# Arduino_extension_connectors.net
KiCad netlist of a schematic drawn in Altium Designer
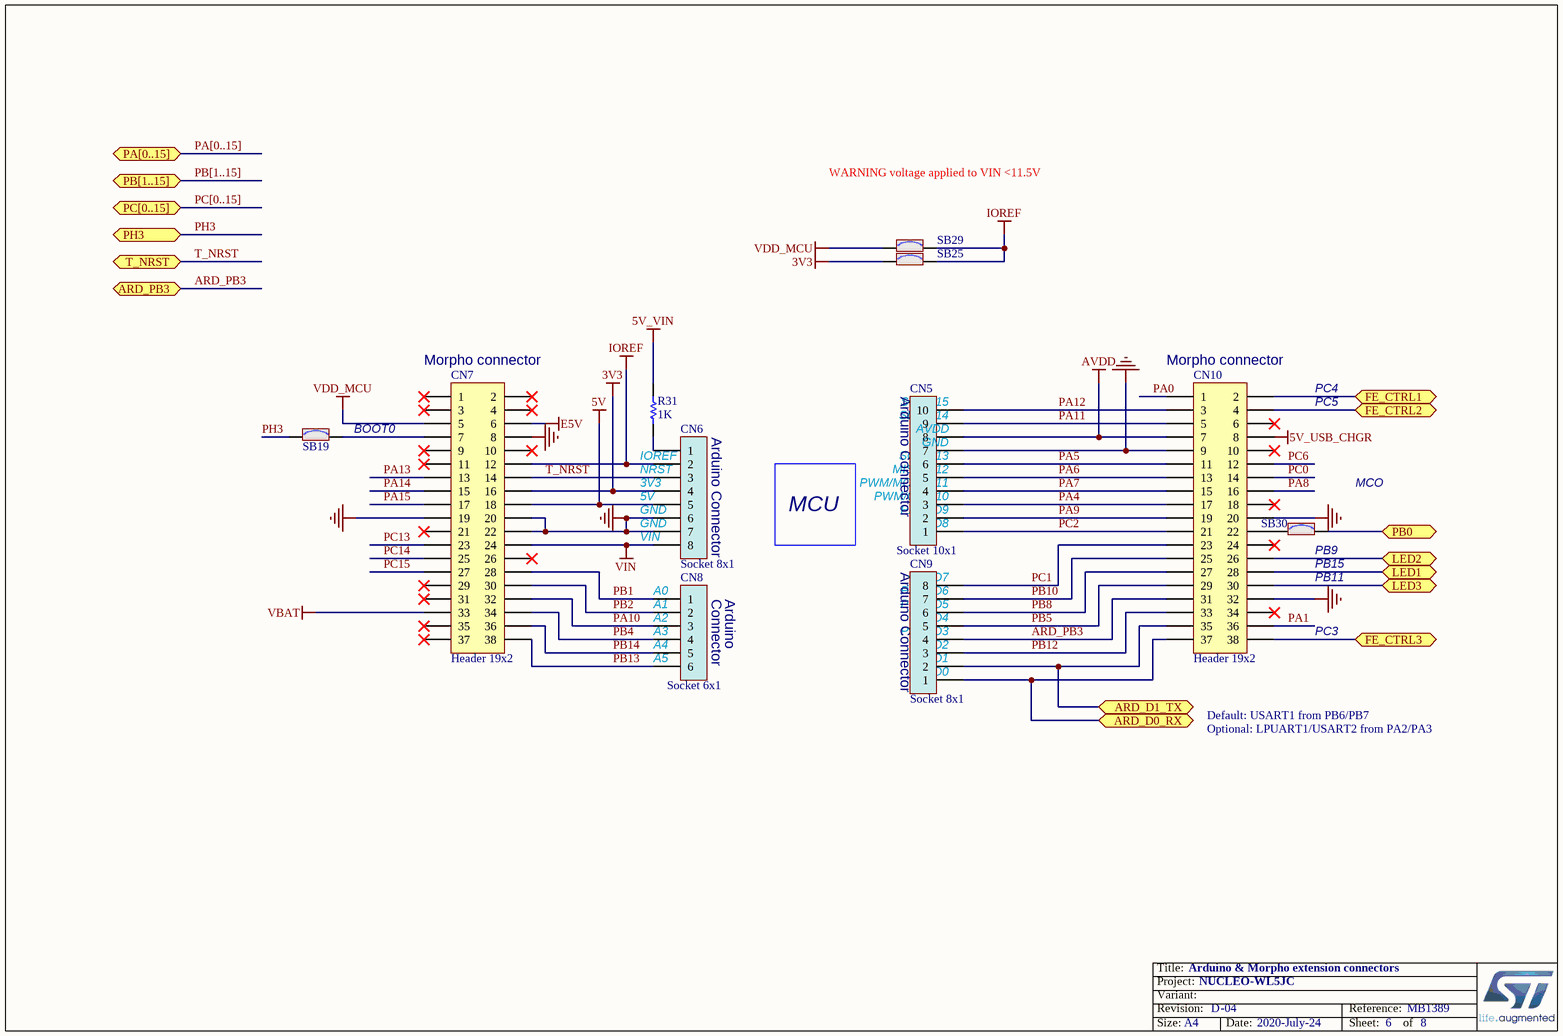
[diagram p0: Arduino_extension_connectors.SchDoc]

(export (version "E")
  (design (tool "Eeschema 10.0.6"))
  (components
    (comp (ref "CN5")
      (value "Socket 10x1")
      (footprint "CON_SAMTEC_SSW-110-03-X-S")
      (description "Socket, 10x1, 2.54mm, VR, TH, Height 8.51mm/10mm")
      (fields
        (field (name "INTERNAL_PART_NUMBER") "MCD-00262")
        (field (name "MANUFACTURER_PART_NUMBER") "SSW-110-03-x-S")
        (field (name "PROVIDED_BY") "SUBCO")
      )
      (libsource (lib "MCD_PARTS_database") (part "Socket 10x1"))
    )
    (comp (ref "CN6")
      (value "Socket 8x1")
      (footprint "CON_SAMTEC_SSW-108-03-X-S")
      (description "Socket, 8x1, 2.54mm, VR, TH, Height 8.51mm/10mm")
      (fields
        (field (name "INTERNAL_PART_NUMBER") "MCD-00261")
        (field (name "MANUFACTURER_PART_NUMBER") "SSW-108-03-x-S")
        (field (name "PROVIDED_BY") "SUBCO")
      )
      (libsource (lib "") (part "Socket 8x1_1"))
    )
    (comp (ref "CN7")
      (value "Header 19x2")
      (footprint "CON_SAMTEC_TSW-119-09-X-D")
      (description "Header, 19x2, 2,54mm, VR, TH, Height 5.84mm/10.16mm")
      (fields
        (field (name "INTERNAL_PART_NUMBER") "MCD-00213")
        (field (name "MANUFACTURER_PART_NUMBER") "TSW-119-09-x-D")
        (field (name "PROVIDED_BY") "SUBCO")
      )
      (libsource (lib "MCD_PARTS_database") (part "Header 19x2"))
    )
    (comp (ref "CN8")
      (value "Socket 6x1")
      (footprint "CON_SAMTEC_SSW-106-03-X-S")
      (description "Socket, 6x1, 2.54mm, VR, TH, Height 8.51mm/10mm")
      (fields
        (field (name "INTERNAL_PART_NUMBER") "MCD-00260")
        (field (name "MANUFACTURER_PART_NUMBER") "SSW-106-03-x-S")
        (field (name "PROVIDED_BY") "SUBCO")
      )
      (libsource (lib "MCD_PARTS_database") (part "Socket 6x1"))
    )
    (comp (ref "CN9")
      (value "Socket 8x1")
      (footprint "CON_SAMTEC_SSW-108-03-X-S")
      (description "Socket, 8x1, 2.54mm, VR, TH, Height 8.51mm/10mm")
      (fields
        (field (name "INTERNAL_PART_NUMBER") "MCD-00261")
        (field (name "MANUFACTURER_PART_NUMBER") "SSW-108-03-x-S")
        (field (name "PROVIDED_BY") "SUBCO")
      )
      (libsource (lib "MCD_PARTS_database") (part "Socket 8x1"))
    )
    (comp (ref "CN10")
      (value "Header 19x2")
      (footprint "CON_SAMTEC_TSW-119-09-X-D")
      (description "Header, 19x2, 2,54mm, VR, TH, Height 5.84mm/10.16mm")
      (fields
        (field (name "INTERNAL_PART_NUMBER") "MCD-00213")
        (field (name "MANUFACTURER_PART_NUMBER") "TSW-119-09-x-D")
        (field (name "PROVIDED_BY") "SUBCO")
      )
      (libsource (lib "MCD_PARTS_database") (part "Header 19x2"))
    )
    (comp (ref "R31")
      (value "1K")
      (footprint "R0603")
      (description "Resistor,1K,0603,1%,1/10W")
      (fields
        (field (name "INTERNAL_PART_NUMBER") "MCD-00070")
        (field (name "MANUFACTURER_PART_NUMBER") "RC0603FR-071KL")
        (field (name "PROVIDED_BY") "SUBCO")
      )
      (libsource (lib "MCD_PARTS_database") (part "Resistor"))
    )
    (comp (ref "SB19")
      (value "~")
      (footprint "SOLDER-BRIDGE_R0603-0R")
      (description "Solder Bridge ON")
      (fields
        (field (name "INTERNAL_PART_NUMBER") "MCD-00071")
        (field (name "MANUFACTURER_PART_NUMBER") "RC0603JR-070RL")
        (field (name "PROVIDED_BY") "SUBCO")
      )
      (libsource (lib "MCD_PARTS_database") (part "SB_ON"))
    )
    (comp (ref "SB25")
      (value "~")
      (footprint "SOLDER-BRIDGE_R0603-0R")
      (description "Solder Bridge ON")
      (fields
        (field (name "INTERNAL_PART_NUMBER") "MCD-00071")
        (field (name "MANUFACTURER_PART_NUMBER") "RC0603JR-070RL")
        (field (name "PROVIDED_BY") "SUBCO")
      )
      (libsource (lib "MCD_PARTS_database") (part "SB_ON"))
    )
    (comp (ref "SB29")
      (value "~")
      (footprint "SOLDER-BRIDGE_R0603-0R")
      (description "Solder Bridge ON")
      (fields
        (field (name "INTERNAL_PART_NUMBER") "MCD-00071")
        (field (name "MANUFACTURER_PART_NUMBER") "RC0603JR-070RL")
        (field (name "PROVIDED_BY") "SUBCO")
      )
      (libsource (lib "MCD_PARTS_database") (part "SB_ON"))
    )
    (comp (ref "SB30")
      (value "~")
      (footprint "SOLDER-BRIDGE_R0603-0R")
      (description "Solder Bridge ON")
      (fields
        (field (name "INTERNAL_PART_NUMBER") "MCD-00071")
        (field (name "MANUFACTURER_PART_NUMBER") "RC0603JR-070RL")
        (field (name "PROVIDED_BY") "SUBCO")
      )
      (libsource (lib "MCD_PARTS_database") (part "SB_ON"))
    )
  )
  (nets
    (net (code "18") (name "/ARD_D0_RX") (class "Default")
      (node (ref "CN10") (pin "37") (pinfunction "37_37") (pintype "passive"))
      (node (ref "CN9") (pin "1") (pinfunction "1_1") (pintype "passive"))
    )
    (net (code "19") (name "/ARD_D1_TX") (class "Default")
      (node (ref "CN10") (pin "35") (pinfunction "35_35") (pintype "passive"))
      (node (ref "CN9") (pin "2") (pinfunction "2_2") (pintype "passive"))
    )
    (net (code "20") (name "/ARD_PB3") (class "Default")
      (node (ref "CN10") (pin "31") (pinfunction "31_31") (pintype "passive"))
      (node (ref "CN9") (pin "4") (pinfunction "4_4") (pintype "passive"))
    )
    (net (code "21") (name "/FE_CTRL1") (class "Default")
      (node (ref "CN10") (pin "2") (pinfunction "2_2") (pintype "passive"))
    )
    (net (code "22") (name "/FE_CTRL2") (class "Default")
      (node (ref "CN10") (pin "4") (pinfunction "4_4") (pintype "passive"))
    )
    (net (code "23") (name "/FE_CTRL3") (class "Default")
      (node (ref "CN10") (pin "38") (pinfunction "38_38") (pintype "passive"))
    )
    (net (code "24") (name "/LED1") (class "Default")
      (node (ref "CN10") (pin "28") (pinfunction "28_28") (pintype "passive"))
    )
    (net (code "25") (name "/LED2") (class "Default")
      (node (ref "CN10") (pin "26") (pinfunction "26_26") (pintype "passive"))
    )
    (net (code "26") (name "/LED3") (class "Default")
      (node (ref "CN10") (pin "30") (pinfunction "30_30") (pintype "passive"))
    )
    (net (code "27") (name "/PA0") (class "Default")
      (node (ref "CN10") (pin "1") (pinfunction "1_1") (pintype "passive"))
    )
    (net (code "28") (name "/PA1") (class "Default")
      (node (ref "CN10") (pin "36") (pinfunction "36_36") (pintype "passive"))
    )
    (net (code "29") (name "/PA4") (class "Default")
      (node (ref "CN10") (pin "17") (pinfunction "17_17") (pintype "passive"))
      (node (ref "CN5") (pin "3") (pinfunction "3_3") (pintype "passive"))
    )
    (net (code "30") (name "/PA5") (class "Default")
      (node (ref "CN10") (pin "11") (pinfunction "11_11") (pintype "passive"))
      (node (ref "CN5") (pin "6") (pinfunction "6_6") (pintype "passive"))
    )
    (net (code "31") (name "/PA6") (class "Default")
      (node (ref "CN10") (pin "13") (pinfunction "13_13") (pintype "passive"))
      (node (ref "CN5") (pin "5") (pinfunction "5_5") (pintype "passive"))
    )
    (net (code "32") (name "/PA7") (class "Default")
      (node (ref "CN10") (pin "15") (pinfunction "15_15") (pintype "passive"))
      (node (ref "CN5") (pin "4") (pinfunction "4_4") (pintype "passive"))
    )
    (net (code "33") (name "/PA8") (class "Default")
      (node (ref "CN10") (pin "16") (pinfunction "16_16") (pintype "passive"))
    )
    (net (code "34") (name "/PA9") (class "Default")
      (node (ref "CN10") (pin "19") (pinfunction "19_19") (pintype "passive"))
      (node (ref "CN5") (pin "2") (pinfunction "2_2") (pintype "passive"))
    )
    (net (code "35") (name "/PA10") (class "Default")
      (node (ref "CN7") (pin "32") (pinfunction "32_32") (pintype "passive"))
      (node (ref "CN8") (pin "3") (pinfunction "3_3") (pintype "passive"))
    )
    (net (code "36") (name "/PA11") (class "Default")
      (node (ref "CN10") (pin "5") (pinfunction "5_5") (pintype "passive"))
      (node (ref "CN5") (pin "9") (pinfunction "9_9") (pintype "passive"))
    )
    (net (code "37") (name "/PA12") (class "Default")
      (node (ref "CN10") (pin "3") (pinfunction "3_3") (pintype "passive"))
      (node (ref "CN5") (pin "10") (pinfunction "10_10") (pintype "passive"))
    )
    (net (code "38") (name "/PA13") (class "Default")
      (node (ref "CN7") (pin "13") (pinfunction "13_13") (pintype "passive"))
    )
    (net (code "39") (name "/PA14") (class "Default")
      (node (ref "CN7") (pin "15") (pinfunction "15_15") (pintype "passive"))
    )
    (net (code "40") (name "/PA15") (class "Default")
      (node (ref "CN7") (pin "17") (pinfunction "17_17") (pintype "passive"))
    )
    (net (code "42") (name "/PB0") (class "Default")
      (node (ref "SB30") (pin "2") (pinfunction "2_2") (pintype "passive"))
    )
    (net (code "43") (name "/PB1") (class "Default")
      (node (ref "CN7") (pin "28") (pinfunction "28_28") (pintype "passive"))
      (node (ref "CN8") (pin "1") (pinfunction "1_1") (pintype "passive"))
    )
    (net (code "44") (name "/PB2") (class "Default")
      (node (ref "CN7") (pin "30") (pinfunction "30_30") (pintype "passive"))
      (node (ref "CN8") (pin "2") (pinfunction "2_2") (pintype "passive"))
    )
    (net (code "45") (name "/PB4") (class "Default")
      (node (ref "CN7") (pin "34") (pinfunction "34_34") (pintype "passive"))
      (node (ref "CN8") (pin "4") (pinfunction "4_4") (pintype "passive"))
    )
    (net (code "46") (name "/PB5") (class "Default")
      (node (ref "CN10") (pin "29") (pinfunction "29_29") (pintype "passive"))
      (node (ref "CN9") (pin "5") (pinfunction "5_5") (pintype "passive"))
    )
    (net (code "47") (name "/PB8") (class "Default")
      (node (ref "CN10") (pin "27") (pinfunction "27_27") (pintype "passive"))
      (node (ref "CN9") (pin "6") (pinfunction "6_6") (pintype "passive"))
    )
    (net (code "48") (name "/PB10") (class "Default")
      (node (ref "CN10") (pin "25") (pinfunction "25_25") (pintype "passive"))
      (node (ref "CN9") (pin "7") (pinfunction "7_7") (pintype "passive"))
    )
    (net (code "49") (name "/PB12") (class "Default")
      (node (ref "CN10") (pin "33") (pinfunction "33_33") (pintype "passive"))
      (node (ref "CN9") (pin "3") (pinfunction "3_3") (pintype "passive"))
    )
    (net (code "50") (name "/PB13") (class "Default")
      (node (ref "CN7") (pin "38") (pinfunction "38_38") (pintype "passive"))
      (node (ref "CN8") (pin "6") (pinfunction "6_6") (pintype "passive"))
    )
    (net (code "51") (name "/PB14") (class "Default")
      (node (ref "CN7") (pin "36") (pinfunction "36_36") (pintype "passive"))
      (node (ref "CN8") (pin "5") (pinfunction "5_5") (pintype "passive"))
    )
    (net (code "53") (name "/PC0") (class "Default")
      (node (ref "CN10") (pin "14") (pinfunction "14_14") (pintype "passive"))
    )
    (net (code "54") (name "/PC1") (class "Default")
      (node (ref "CN10") (pin "23") (pinfunction "23_23") (pintype "passive"))
      (node (ref "CN9") (pin "8") (pinfunction "8_8") (pintype "passive"))
    )
    (net (code "55") (name "/PC2") (class "Default")
      (node (ref "CN10") (pin "21") (pinfunction "21_21") (pintype "passive"))
      (node (ref "CN5") (pin "1") (pinfunction "1_1") (pintype "passive"))
    )
    (net (code "56") (name "/PC6") (class "Default")
      (node (ref "CN10") (pin "12") (pinfunction "12_12") (pintype "passive"))
    )
    (net (code "57") (name "/PC13") (class "Default")
      (node (ref "CN7") (pin "23") (pinfunction "23_23") (pintype "passive"))
    )
    (net (code "58") (name "/PC14") (class "Default")
      (node (ref "CN7") (pin "25") (pinfunction "25_25") (pintype "passive"))
    )
    (net (code "59") (name "/PC15") (class "Default")
      (node (ref "CN7") (pin "27") (pinfunction "27_27") (pintype "passive"))
    )
    (net (code "61") (name "/PH3") (class "Default")
      (node (ref "SB19") (pin "1") (pinfunction "1_1") (pintype "passive"))
    )
    (net (code "62") (name "/T_NRST") (class "Default")
      (node (ref "CN6") (pin "3") (pinfunction "3_3") (pintype "passive"))
      (node (ref "CN7") (pin "14") (pinfunction "14_14") (pintype "passive"))
    )
    (net (code "63") (name "3V3") (class "Default")
      (node (ref "CN6") (pin "4") (pinfunction "4_4") (pintype "passive"))
      (node (ref "CN7") (pin "16") (pinfunction "16_16") (pintype "passive"))
      (node (ref "SB25") (pin "1") (pinfunction "1_1") (pintype "passive"))
    )
    (net (code "64") (name "5V") (class "Default")
      (node (ref "CN6") (pin "5") (pinfunction "5_5") (pintype "passive"))
      (node (ref "CN7") (pin "18") (pinfunction "18_18") (pintype "passive"))
    )
    (net (code "65") (name "5V_USB_CHGR") (class "Default")
      (node (ref "CN10") (pin "8") (pinfunction "8_8") (pintype "passive"))
    )
    (net (code "66") (name "5V_VIN") (class "Default")
      (node (ref "R31") (pin "2") (pinfunction "2_2") (pintype "passive"))
    )
    (net (code "67") (name "AVDD") (class "Default")
      (node (ref "CN10") (pin "7") (pinfunction "7_7") (pintype "passive"))
      (node (ref "CN5") (pin "8") (pinfunction "8_8") (pintype "passive"))
    )
    (net (code "68") (name "E5V") (class "Default")
      (node (ref "CN7") (pin "6") (pinfunction "6_6") (pintype "passive"))
    )
    (net (code "69") (name "GND") (class "Default")
      (node (ref "CN10") (pin "20") (pinfunction "20_20") (pintype "passive"))
      (node (ref "CN10") (pin "32") (pinfunction "32_32") (pintype "passive"))
      (node (ref "CN10") (pin "9") (pinfunction "9_9") (pintype "passive"))
      (node (ref "CN5") (pin "7") (pinfunction "7_7") (pintype "passive"))
      (node (ref "CN6") (pin "6") (pinfunction "6_6") (pintype "passive"))
      (node (ref "CN6") (pin "7") (pinfunction "7_7") (pintype "passive"))
      (node (ref "CN7") (pin "19") (pinfunction "19_19") (pintype "passive"))
      (node (ref "CN7") (pin "20") (pinfunction "20_20") (pintype "passive"))
      (node (ref "CN7") (pin "22") (pinfunction "22_22") (pintype "passive"))
      (node (ref "CN7") (pin "8") (pinfunction "8_8") (pintype "passive"))
    )
    (net (code "70") (name "IOREF") (class "Default")
      (node (ref "CN6") (pin "2") (pinfunction "2_2") (pintype "passive"))
      (node (ref "CN7") (pin "12") (pinfunction "12_12") (pintype "passive"))
      (node (ref "SB25") (pin "2") (pinfunction "2_2") (pintype "passive"))
      (node (ref "SB29") (pin "2") (pinfunction "2_2") (pintype "passive"))
    )
    (net (code "71") (name "Net-(CN6-Pad1)") (class "Default")
      (node (ref "CN6") (pin "1") (pinfunction "1_1") (pintype "passive"))
      (node (ref "R31") (pin "1") (pinfunction "1_1") (pintype "passive"))
    )
    (net (code "72") (name "Net-(CN7-Pad7)") (class "Default")
      (node (ref "CN7") (pin "7") (pinfunction "7_7") (pintype "passive"))
      (node (ref "SB19") (pin "2") (pinfunction "2_2") (pintype "passive"))
    )
    (net (code "73") (name "Net-(CN10-Pad22)") (class "Default")
      (node (ref "CN10") (pin "22") (pinfunction "22_22") (pintype "passive"))
      (node (ref "SB30") (pin "1") (pinfunction "1_1") (pintype "passive"))
    )
    (net (code "74") (name "VBAT") (class "Default")
      (node (ref "CN7") (pin "33") (pinfunction "33_33") (pintype "passive"))
    )
    (net (code "75") (name "VDD_MCU") (class "Default")
      (node (ref "CN7") (pin "5") (pinfunction "5_5") (pintype "passive"))
      (node (ref "SB29") (pin "1") (pinfunction "1_1") (pintype "passive"))
    )
    (net (code "76") (name "VIN") (class "Default")
      (node (ref "CN6") (pin "8") (pinfunction "8_8") (pintype "passive"))
      (node (ref "CN7") (pin "24") (pinfunction "24_24") (pintype "passive"))
    )
    (net (code "77") (name "unconnected-(CN7-Pad1)") (class "Default")
      (node (ref "CN7") (pin "1") (pinfunction "1_1") (pintype "passive+no_connect"))
    )
    (net (code "78") (name "unconnected-(CN7-Pad2)") (class "Default")
      (node (ref "CN7") (pin "2") (pinfunction "2_2") (pintype "passive+no_connect"))
    )
    (net (code "79") (name "unconnected-(CN7-Pad3)") (class "Default")
      (node (ref "CN7") (pin "3") (pinfunction "3_3") (pintype "passive+no_connect"))
    )
    (net (code "80") (name "unconnected-(CN7-Pad4)") (class "Default")
      (node (ref "CN7") (pin "4") (pinfunction "4_4") (pintype "passive+no_connect"))
    )
    (net (code "81") (name "unconnected-(CN7-Pad9)") (class "Default")
      (node (ref "CN7") (pin "9") (pinfunction "9_9") (pintype "passive+no_connect"))
    )
    (net (code "82") (name "unconnected-(CN7-Pad10)") (class "Default")
      (node (ref "CN7") (pin "10") (pinfunction "10_10") (pintype "passive+no_connect"))
    )
    (net (code "83") (name "unconnected-(CN7-Pad11)") (class "Default")
      (node (ref "CN7") (pin "11") (pinfunction "11_11") (pintype "passive+no_connect"))
    )
    (net (code "84") (name "unconnected-(CN7-Pad21)") (class "Default")
      (node (ref "CN7") (pin "21") (pinfunction "21_21") (pintype "passive+no_connect"))
    )
    (net (code "85") (name "unconnected-(CN7-Pad26)") (class "Default")
      (node (ref "CN7") (pin "26") (pinfunction "26_26") (pintype "passive+no_connect"))
    )
    (net (code "86") (name "unconnected-(CN7-Pad29)") (class "Default")
      (node (ref "CN7") (pin "29") (pinfunction "29_29") (pintype "passive+no_connect"))
    )
    (net (code "87") (name "unconnected-(CN7-Pad31)") (class "Default")
      (node (ref "CN7") (pin "31") (pinfunction "31_31") (pintype "passive+no_connect"))
    )
    (net (code "88") (name "unconnected-(CN7-Pad35)") (class "Default")
      (node (ref "CN7") (pin "35") (pinfunction "35_35") (pintype "passive+no_connect"))
    )
    (net (code "89") (name "unconnected-(CN7-Pad37)") (class "Default")
      (node (ref "CN7") (pin "37") (pinfunction "37_37") (pintype "passive+no_connect"))
    )
    (net (code "90") (name "unconnected-(CN10-Pad6)") (class "Default")
      (node (ref "CN10") (pin "6") (pinfunction "6_6") (pintype "passive+no_connect"))
    )
    (net (code "91") (name "unconnected-(CN10-Pad10)") (class "Default")
      (node (ref "CN10") (pin "10") (pinfunction "10_10") (pintype "passive+no_connect"))
    )
    (net (code "92") (name "unconnected-(CN10-Pad18)") (class "Default")
      (node (ref "CN10") (pin "18") (pinfunction "18_18") (pintype "passive+no_connect"))
    )
    (net (code "93") (name "unconnected-(CN10-Pad24)") (class "Default")
      (node (ref "CN10") (pin "24") (pinfunction "24_24") (pintype "passive+no_connect"))
    )
    (net (code "94") (name "unconnected-(CN10-Pad34)") (class "Default")
      (node (ref "CN10") (pin "34") (pinfunction "34_34") (pintype "passive+no_connect"))
    )
  )
)
